# UART.net
KiCad netlist of a schematic drawn in Altium Designer
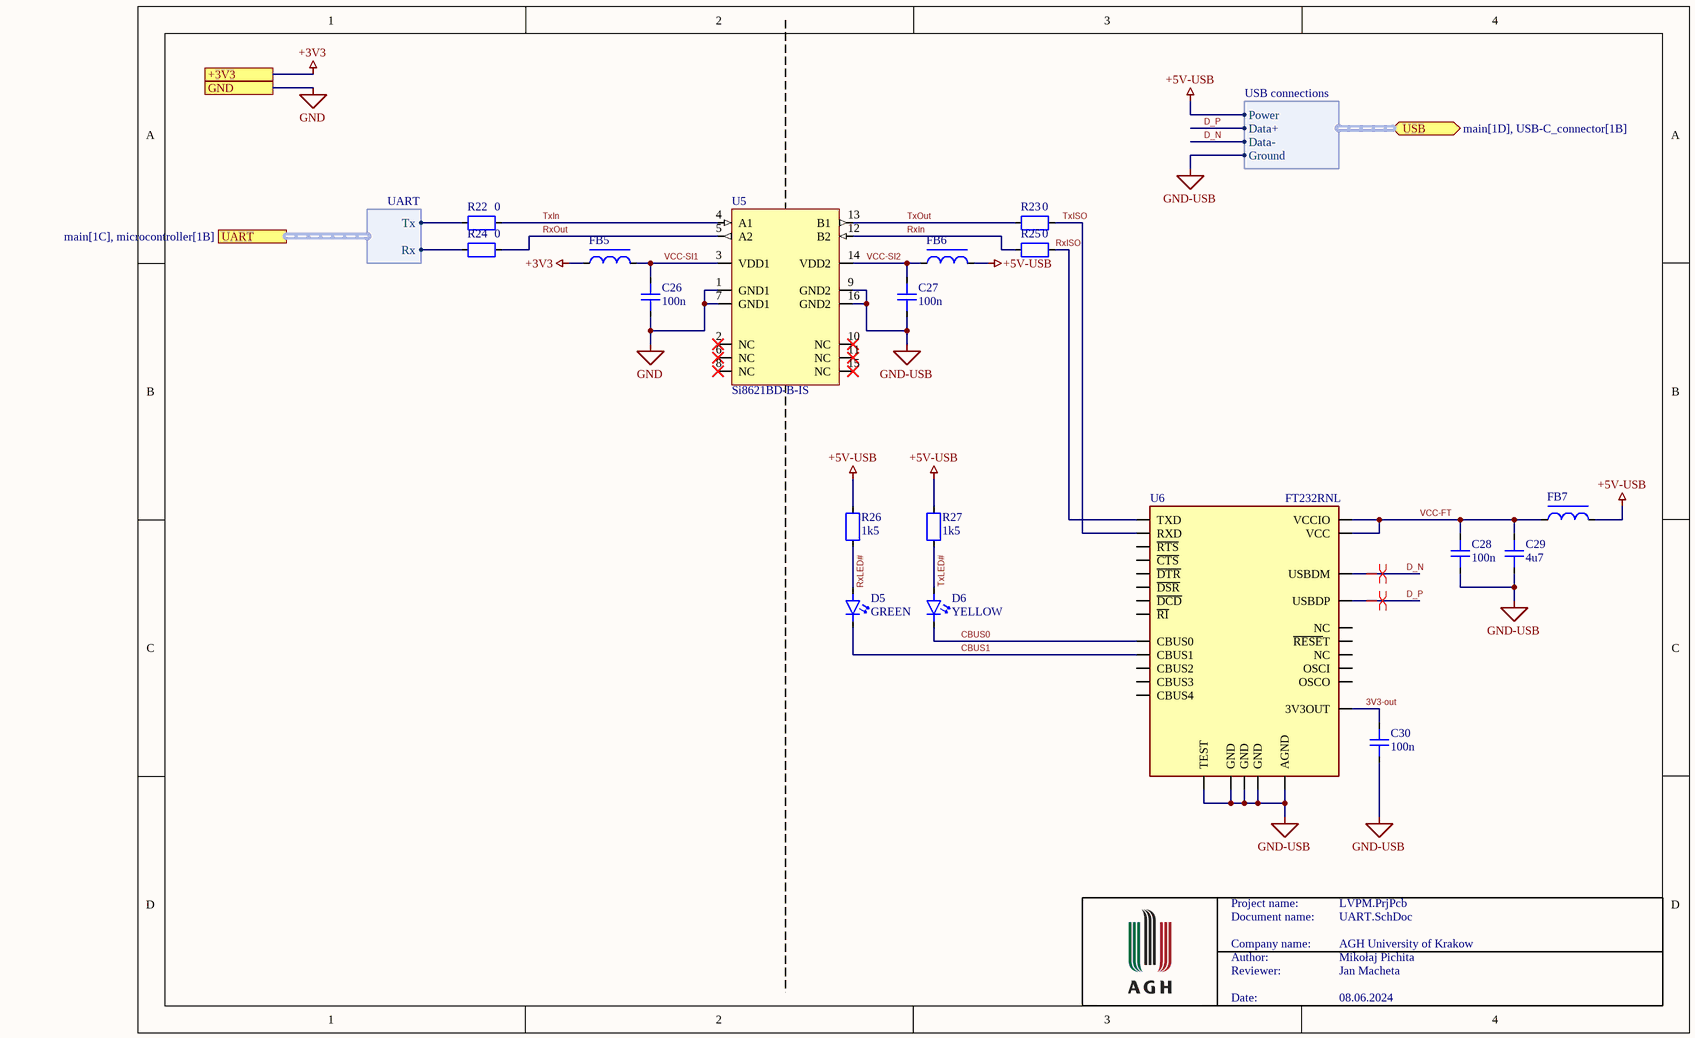
[diagram p0: UART.SchDoc]

(export (version "E")
  (design (tool "Eeschema 10.0.6"))
  (components
    (comp (ref "C26")
      (value "100n")
      (footprint "CAP0603")
      (libsource (lib "Integrated_Library_main") (part "Capacitor"))
    )
    (comp (ref "C27")
      (value "100n")
      (footprint "CAP0603")
      (libsource (lib "Integrated_Library_main") (part "Capacitor"))
    )
    (comp (ref "C28")
      (value "100n")
      (footprint "CAP0603")
      (libsource (lib "Integrated_Library_main") (part "Capacitor"))
    )
    (comp (ref "C29")
      (value "4u7")
      (footprint "CAP0603")
      (libsource (lib "Integrated_Library_main") (part "Capacitor"))
    )
    (comp (ref "C30")
      (value "100n")
      (footprint "CAP0603")
      (libsource (lib "Integrated_Library_main") (part "Capacitor"))
    )
    (comp (ref "D5")
      (value "GREEN")
      (footprint "LED0603")
      (libsource (lib "Integrated_Library_main") (part "LED"))
    )
    (comp (ref "D6")
      (value "YELLOW")
      (footprint "LED0603")
      (libsource (lib "Integrated_Library_main") (part "LED"))
    )
    (comp (ref "FB5")
      (value "*")
      (footprint "FB0402")
      (libsource (lib "Integrated_Library_main") (part "Ferrite Bead"))
    )
    (comp (ref "FB6")
      (value "*")
      (footprint "FB0402")
      (libsource (lib "Integrated_Library_main") (part "Ferrite Bead"))
    )
    (comp (ref "FB7")
      (value "*")
      (footprint "FB0402")
      (libsource (lib "Integrated_Library_main") (part "Ferrite Bead"))
    )
    (comp (ref "R22")
      (value "0")
      (footprint "RES0603")
      (libsource (lib "Integrated_Library_main") (part "Resistor"))
    )
    (comp (ref "R23")
      (value "0")
      (footprint "RES0603")
      (libsource (lib "Integrated_Library_main") (part "Resistor"))
    )
    (comp (ref "R24")
      (value "0")
      (footprint "RES0603")
      (libsource (lib "Integrated_Library_main") (part "Resistor"))
    )
    (comp (ref "R25")
      (value "0")
      (footprint "RES0603")
      (libsource (lib "Integrated_Library_main") (part "Resistor"))
    )
    (comp (ref "R26")
      (value "1k5")
      (footprint "RES0603")
      (libsource (lib "Integrated_Library_main") (part "Resistor"))
    )
    (comp (ref "R27")
      (value "1k5")
      (footprint "RES0603")
      (libsource (lib "Integrated_Library_main") (part "Resistor"))
    )
    (comp (ref "U5")
      (value "Si8621BD-B-IS")
      (footprint "SLAB-SOIC-16-WB_M")
      (fields (field (name "MANUFACTURER") "Silicon Labs"))
      (libsource (lib "Integrated_Library_main") (part "Si8621BD-B-IS"))
    )
    (comp (ref "U6")
      (value "FT232RNL")
      (footprint "SOP65P780X200-28N")
      (description "USB Interface IC USB Full Speed to Serial UART IC, Includes Oscillator and EEPROM, SSOP-28")
      (libsource (lib "Integrated_Library_main") (part "FT232RNL"))
    )
  )
  (nets
    (net (code "4") (name "+3V3") (class "Default") (node (ref "FB5") (pin "1") (pintype "passive")))
    (net (code "5") (name "+5V-USB") (class "Default")
      (node (ref "FB6") (pin "2") (pintype "passive"))
      (node (ref "FB7") (pin "2") (pintype "passive"))
      (node (ref "R26") (pin "1") (pintype "passive"))
      (node (ref "R27") (pin "1") (pintype "passive"))
    )
    (net (code "6") (name "/3V3-out") (class "Default")
      (node (ref "C30") (pin "1") (pintype "passive"))
      (node (ref "U6") (pin "17") (pinfunction "3V3OUT_17") (pintype "passive"))
    )
    (net (code "7") (name "/CBUS0") (class "Default")
      (node (ref "D6") (pin "2") (pintype "passive"))
      (node (ref "U6") (pin "23") (pinfunction "CBUS0_23") (pintype "passive"))
    )
    (net (code "8") (name "/CBUS1") (class "Default")
      (node (ref "D5") (pin "2") (pintype "passive"))
      (node (ref "U6") (pin "22") (pinfunction "CBUS1_22") (pintype "passive"))
    )
    (net (code "9") (name "/D_N") (class "Default")
      (node (ref "U6") (pin "16") (pinfunction "USBDM_16") (pintype "passive"))
    )
    (net (code "10") (name "/D_P") (class "Default")
      (node (ref "U6") (pin "15") (pinfunction "USBDP_15") (pintype "passive"))
    )
    (net (code "11") (name "/Rx") (class "Default") (node (ref "R24") (pin "2") (pintype "passive")))
    (net (code "12") (name "/RxISO") (class "Default")
      (node (ref "R25") (pin "1") (pintype "passive"))
      (node (ref "U6") (pin "1") (pinfunction "TXD_1") (pintype "passive"))
    )
    (net (code "13") (name "/RxIn") (class "Default")
      (node (ref "R25") (pin "2") (pintype "passive"))
      (node (ref "U5") (pin "12") (pinfunction "B2_12") (pintype "input"))
    )
    (net (code "14") (name "/RxLED#") (class "Default")
      (node (ref "D5") (pin "1") (pintype "passive"))
      (node (ref "R26") (pin "2") (pintype "passive"))
    )
    (net (code "15") (name "/RxOut") (class "Default")
      (node (ref "R24") (pin "1") (pintype "passive"))
      (node (ref "U5") (pin "5") (pinfunction "A2_5") (pintype "output"))
    )
    (net (code "16") (name "/Tx") (class "Default") (node (ref "R22") (pin "2") (pintype "passive")))
    (net (code "17") (name "/TxISO") (class "Default")
      (node (ref "R23") (pin "1") (pintype "passive"))
      (node (ref "U6") (pin "5") (pinfunction "RXD_5") (pintype "passive"))
    )
    (net (code "18") (name "/TxIn") (class "Default")
      (node (ref "R22") (pin "1") (pintype "passive"))
      (node (ref "U5") (pin "4") (pinfunction "A1_4") (pintype "input"))
    )
    (net (code "19") (name "/TxLED#") (class "Default")
      (node (ref "D6") (pin "1") (pintype "passive"))
      (node (ref "R27") (pin "2") (pintype "passive"))
    )
    (net (code "20") (name "/TxOut") (class "Default")
      (node (ref "R23") (pin "2") (pintype "passive"))
      (node (ref "U5") (pin "13") (pinfunction "B1_13") (pintype "output"))
    )
    (net (code "21") (name "/VCC-FT") (class "Default")
      (node (ref "C28") (pin "1") (pintype "passive"))
      (node (ref "C29") (pin "1") (pintype "passive"))
      (node (ref "FB7") (pin "1") (pintype "passive"))
      (node (ref "U6") (pin "20") (pinfunction "VCC_20") (pintype "passive"))
      (node (ref "U6") (pin "4") (pinfunction "VCCIO_4") (pintype "passive"))
    )
    (net (code "22") (name "/VCC-SI1") (class "Default")
      (node (ref "C26") (pin "1") (pintype "passive"))
      (node (ref "FB5") (pin "2") (pintype "passive"))
      (node (ref "U5") (pin "3") (pinfunction "VDD1_3") (pintype "power_in"))
    )
    (net (code "23") (name "/VCC-SI2") (class "Default")
      (node (ref "C27") (pin "1") (pintype "passive"))
      (node (ref "FB6") (pin "1") (pintype "passive"))
      (node (ref "U5") (pin "14") (pinfunction "VDD2_14") (pintype "power_in"))
    )
    (net (code "26") (name "GND") (class "Default")
      (node (ref "C26") (pin "2") (pintype "passive"))
      (node (ref "U5") (pin "1") (pinfunction "GND1_1") (pintype "power_in"))
      (node (ref "U5") (pin "7") (pinfunction "GND1_7") (pintype "passive"))
    )
    (net (code "27") (name "GND-USB") (class "Default")
      (node (ref "C27") (pin "2") (pintype "passive"))
      (node (ref "C28") (pin "2") (pintype "passive"))
      (node (ref "C29") (pin "2") (pintype "passive"))
      (node (ref "C30") (pin "2") (pintype "passive"))
      (node (ref "U5") (pin "16") (pinfunction "GND2_16") (pintype "passive"))
      (node (ref "U5") (pin "9") (pinfunction "GND2_9") (pintype "power_in"))
      (node (ref "U6") (pin "18") (pinfunction "GND_18") (pintype "passive"))
      (node (ref "U6") (pin "21") (pinfunction "GND_21") (pintype "passive"))
      (node (ref "U6") (pin "25") (pinfunction "AGND_25") (pintype "passive"))
      (node (ref "U6") (pin "26") (pinfunction "TEST_26") (pintype "passive"))
      (node (ref "U6") (pin "7") (pinfunction "GND_7") (pintype "passive"))
    )
    (net (code "28") (name "unconnected-(U5-NC-Pad2)") (class "Default")
      (node (ref "U5") (pin "2") (pinfunction "NC_2") (pintype "passive+no_connect"))
    )
    (net (code "29") (name "unconnected-(U5-NC-Pad6)") (class "Default")
      (node (ref "U5") (pin "6") (pinfunction "NC_6") (pintype "passive+no_connect"))
    )
    (net (code "30") (name "unconnected-(U5-NC-Pad8)") (class "Default")
      (node (ref "U5") (pin "8") (pinfunction "NC_8") (pintype "passive+no_connect"))
    )
    (net (code "31") (name "unconnected-(U5-NC-Pad10)") (class "Default")
      (node (ref "U5") (pin "10") (pinfunction "NC_10") (pintype "passive+no_connect"))
    )
    (net (code "32") (name "unconnected-(U5-NC-Pad11)") (class "Default")
      (node (ref "U5") (pin "11") (pinfunction "NC_11") (pintype "passive+no_connect"))
    )
    (net (code "33") (name "unconnected-(U5-NC-Pad15)") (class "Default")
      (node (ref "U5") (pin "15") (pinfunction "NC_15") (pintype "passive+no_connect"))
    )
    (net (code "34") (name "unconnected-(U6-CBUS2-Pad13)") (class "Default")
      (node (ref "U6") (pin "13") (pinfunction "CBUS2_13") (pintype "passive"))
    )
    (net (code "35") (name "unconnected-(U6-CBUS3-Pad14)") (class "Default")
      (node (ref "U6") (pin "14") (pinfunction "CBUS3_14") (pintype "passive"))
    )
    (net (code "36") (name "unconnected-(U6-CBUS4-Pad12)") (class "Default")
      (node (ref "U6") (pin "12") (pinfunction "CBUS4_12") (pintype "passive"))
    )
    (net (code "37") (name "unconnected-(U6-NC-Pad8)") (class "Default")
      (node (ref "U6") (pin "8") (pinfunction "NC_8") (pintype "passive"))
    )
    (net (code "38") (name "unconnected-(U6-NC-Pad24)") (class "Default")
      (node (ref "U6") (pin "24") (pinfunction "NC_24") (pintype "passive"))
    )
    (net (code "39") (name "unconnected-(U6-OSCI-Pad27)") (class "Default")
      (node (ref "U6") (pin "27") (pinfunction "OSCI_27") (pintype "passive"))
    )
    (net (code "40") (name "unconnected-(U6-OSCO-Pad28)") (class "Default")
      (node (ref "U6") (pin "28") (pinfunction "OSCO_28") (pintype "passive"))
    )
    (net (code "41") (name "unconnected-(U6-~{CTS}-Pad11)") (class "Default")
      (node (ref "U6") (pin "11") (pinfunction "~{CTS}_11") (pintype "passive"))
    )
    (net (code "42") (name "unconnected-(U6-~{DCD}-Pad10)") (class "Default")
      (node (ref "U6") (pin "10") (pinfunction "~{DCD}_10") (pintype "passive"))
    )
    (net (code "43") (name "unconnected-(U6-~{DSR}-Pad9)") (class "Default")
      (node (ref "U6") (pin "9") (pinfunction "~{DSR}_9") (pintype "passive"))
    )
    (net (code "44") (name "unconnected-(U6-~{DTR}-Pad2)") (class "Default")
      (node (ref "U6") (pin "2") (pinfunction "~{DTR}_2") (pintype "passive"))
    )
    (net (code "45") (name "unconnected-(U6-~{RESE}T-Pad19)") (class "Default")
      (node (ref "U6") (pin "19") (pinfunction "~{RESE}T_19") (pintype "passive"))
    )
    (net (code "46") (name "unconnected-(U6-~{RI}-Pad6)") (class "Default")
      (node (ref "U6") (pin "6") (pinfunction "~{RI}_6") (pintype "passive"))
    )
    (net (code "47") (name "unconnected-(U6-~{RTS}-Pad3)") (class "Default")
      (node (ref "U6") (pin "3") (pinfunction "~{RTS}_3") (pintype "passive"))
    )
  )
)
